# Power.net
KiCad netlist of a schematic drawn in Altium Designer
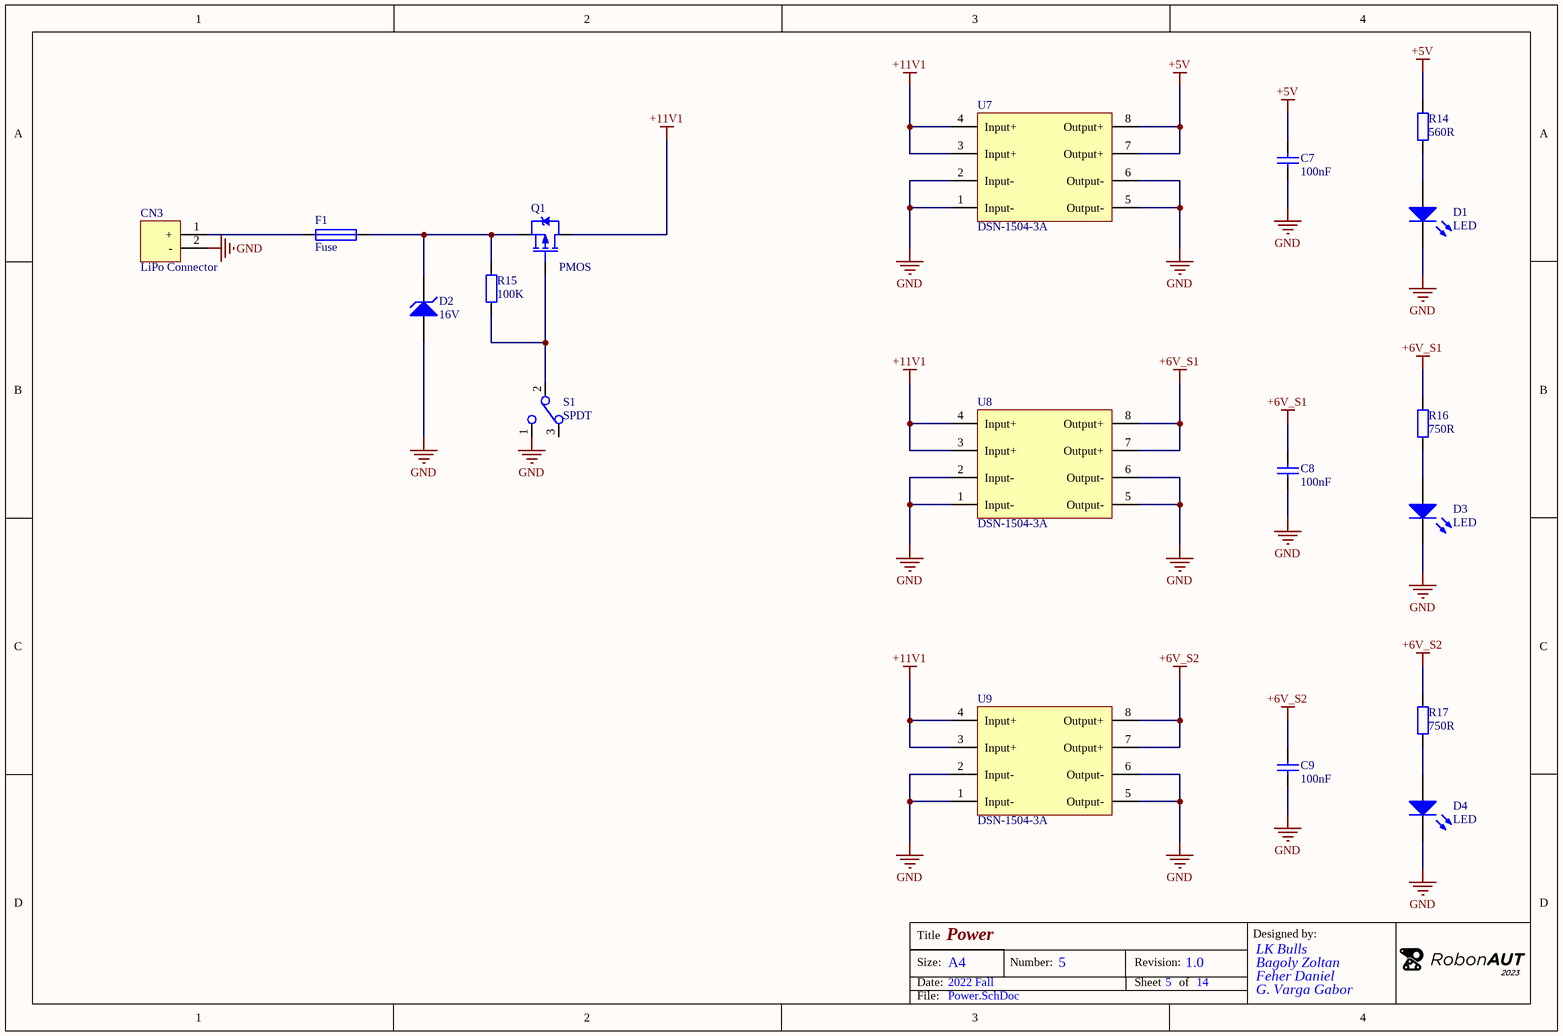
[diagram p0: Power.SchDoc]

(export (version "E")
  (design (tool "Eeschema 10.0.6"))
  (components
    (comp (ref "C7")
      (value "100nF")
      (footprint "FP_0805_CAP_085")
      (description "Capacitor")
      (fields (field (name "TOLERANCE") "10%") (field (name "VOLTAGE") "50V"))
      (libsource (lib "LKBulls2023") (part "CAP"))
    )
    (comp (ref "C8")
      (value "100nF")
      (footprint "FP_0805_CAP_085")
      (description "Capacitor")
      (fields (field (name "TOLERANCE") "10%") (field (name "VOLTAGE") "50V"))
      (libsource (lib "LKBulls2023") (part "CAP"))
    )
    (comp (ref "C9")
      (value "100nF")
      (footprint "FP_0805_CAP_085")
      (description "Capacitor")
      (fields (field (name "TOLERANCE") "10%") (field (name "VOLTAGE") "50V"))
      (libsource (lib "LKBulls2023") (part "CAP"))
    )
    (comp (ref "CN3")
      (value "LiPo Connector")
      (footprint "FP_BATTERY")
      (description "LiPo Battery Connector")
      (libsource (lib "LKBulls2023") (part "Connector_LiPo"))
    )
    (comp (ref "D1")
      (value "LED")
      (footprint "FP_0805_LED_GREEN")
      (description "Typical RED GaAs LED")
      (libsource (lib "LKBulls2023") (part "LED"))
    )
    (comp (ref "D2")
      (value "16V")
      (footprint "FP_SOD-123")
      (description "Zener Diode")
      (libsource (lib "LKBulls2023") (part "ZENER"))
    )
    (comp (ref "D3")
      (value "LED")
      (footprint "FP_0805_LED_GREEN")
      (description "Typical RED GaAs LED")
      (libsource (lib "LKBulls2023") (part "LED"))
    )
    (comp (ref "D4")
      (value "LED")
      (footprint "FP_0805_LED_GREEN")
      (description "Typical RED GaAs LED")
      (libsource (lib "LKBulls2023") (part "LED"))
    )
    (comp (ref "F1")
      (value "Fuse")
      (footprint "FP_CONN2_TUSKE_254MM")
      (libsource (lib "LKBulls2023") (part "Fuse"))
    )
    (comp (ref "Q1")
      (value "PMOS")
      (footprint "FP_DPAK-TO252")
      (description "MOSFET, P CH")
      (libsource (lib "LKBulls2023") (part "PMOS"))
    )
    (comp (ref "R14")
      (value "560R")
      (footprint "FP_0805_RES")
      (description "Resistor")
      (fields (field (name "TOLERANCE") "5%") (field (name "POWER") "0.125W"))
      (libsource (lib "LKBulls2023") (part "RES"))
    )
    (comp (ref "R15")
      (value "100K")
      (footprint "FP_0805_RES")
      (description "Resistor")
      (fields (field (name "TOLERANCE") "5%") (field (name "POWER") "0.125W"))
      (libsource (lib "LKBulls2023") (part "RES"))
    )
    (comp (ref "R16")
      (value "750R")
      (footprint "FP_0805_RES")
      (description "Resistor")
      (fields (field (name "TOLERANCE") "5%") (field (name "POWER") "0.125W"))
      (libsource (lib "LKBulls2023") (part "RES"))
    )
    (comp (ref "R17")
      (value "750R")
      (footprint "FP_0805_RES")
      (description "Resistor")
      (fields (field (name "TOLERANCE") "5%") (field (name "POWER") "0.125W"))
      (libsource (lib "LKBulls2023") (part "RES"))
    )
    (comp (ref "S1")
      (value "SPDT")
      (footprint "FP_SPDT")
      (description "Single-Pole, Double-Throw Switch")
      (libsource (lib "LKBulls2023") (part "SPDT Switch"))
    )
    (comp (ref "U7")
      (value "DSN-1504-3A")
      (footprint "FP_DCDC_DSN")
      (libsource (lib "LKBulls2023") (part "DSN-1504-3A"))
    )
    (comp (ref "U8")
      (value "DSN-1504-3A")
      (footprint "FP_DCDC_DSN")
      (libsource (lib "LKBulls2023") (part "DSN-1504-3A"))
    )
    (comp (ref "U9")
      (value "DSN-1504-3A")
      (footprint "FP_DCDC_DSN")
      (libsource (lib "LKBulls2023") (part "DSN-1504-3A"))
    )
  )
  (nets
    (net (code "1") (name "+5V") (class "Default")
      (node (ref "C7") (pin "2") (pinfunction "2_2") (pintype "passive"))
      (node (ref "R14") (pin "2") (pinfunction "2_2") (pintype "passive"))
      (node (ref "U7") (pin "7") (pinfunction "Output+_7") (pintype "passive"))
      (node (ref "U7") (pin "8") (pinfunction "Output+_8") (pintype "passive"))
    )
    (net (code "2") (name "+6V_S1") (class "Default")
      (node (ref "C8") (pin "2") (pinfunction "2_2") (pintype "passive"))
      (node (ref "R16") (pin "2") (pinfunction "2_2") (pintype "passive"))
      (node (ref "U8") (pin "7") (pinfunction "Output+_7") (pintype "passive"))
      (node (ref "U8") (pin "8") (pinfunction "Output+_8") (pintype "passive"))
    )
    (net (code "3") (name "+6V_S2") (class "Default")
      (node (ref "C9") (pin "2") (pinfunction "2_2") (pintype "passive"))
      (node (ref "R17") (pin "2") (pinfunction "2_2") (pintype "passive"))
      (node (ref "U9") (pin "7") (pinfunction "Output+_7") (pintype "passive"))
      (node (ref "U9") (pin "8") (pinfunction "Output+_8") (pintype "passive"))
    )
    (net (code "4") (name "+11V1") (class "Default")
      (node (ref "Q1") (pin "2") (pinfunction "D_2") (pintype "passive"))
      (node (ref "U7") (pin "3") (pinfunction "Input+_3") (pintype "passive"))
      (node (ref "U7") (pin "4") (pinfunction "Input+_4") (pintype "passive"))
      (node (ref "U8") (pin "3") (pinfunction "Input+_3") (pintype "passive"))
      (node (ref "U8") (pin "4") (pinfunction "Input+_4") (pintype "passive"))
      (node (ref "U9") (pin "3") (pinfunction "Input+_3") (pintype "passive"))
      (node (ref "U9") (pin "4") (pinfunction "Input+_4") (pintype "passive"))
    )
    (net (code "5") (name "GND") (class "Default")
      (node (ref "C7") (pin "1") (pinfunction "1_1") (pintype "passive"))
      (node (ref "C8") (pin "1") (pinfunction "1_1") (pintype "passive"))
      (node (ref "C9") (pin "1") (pinfunction "1_1") (pintype "passive"))
      (node (ref "CN3") (pin "2") (pinfunction "-_2") (pintype "passive"))
      (node (ref "D1") (pin "2") (pinfunction "K_2") (pintype "passive"))
      (node (ref "D2") (pin "A") (pinfunction "1_A") (pintype "passive"))
      (node (ref "D3") (pin "2") (pinfunction "K_2") (pintype "passive"))
      (node (ref "D4") (pin "2") (pinfunction "K_2") (pintype "passive"))
      (node (ref "S1") (pin "1") (pinfunction "C1_1") (pintype "passive"))
      (node (ref "U7") (pin "1") (pinfunction "Input-_1") (pintype "passive"))
      (node (ref "U7") (pin "2") (pinfunction "Input-_2") (pintype "passive"))
      (node (ref "U7") (pin "5") (pinfunction "Output-_5") (pintype "passive"))
      (node (ref "U7") (pin "6") (pinfunction "Output-_6") (pintype "passive"))
      (node (ref "U8") (pin "1") (pinfunction "Input-_1") (pintype "passive"))
      (node (ref "U8") (pin "2") (pinfunction "Input-_2") (pintype "passive"))
      (node (ref "U8") (pin "5") (pinfunction "Output-_5") (pintype "passive"))
      (node (ref "U8") (pin "6") (pinfunction "Output-_6") (pintype "passive"))
      (node (ref "U9") (pin "1") (pinfunction "Input-_1") (pintype "passive"))
      (node (ref "U9") (pin "2") (pinfunction "Input-_2") (pintype "passive"))
      (node (ref "U9") (pin "5") (pinfunction "Output-_5") (pintype "passive"))
      (node (ref "U9") (pin "6") (pinfunction "Output-_6") (pintype "passive"))
    )
    (net (code "6") (name "Net-(CN3-+)") (class "Default")
      (node (ref "CN3") (pin "1") (pinfunction "+_1") (pintype "passive"))
      (node (ref "F1") (pin "1") (pinfunction "1_1") (pintype "passive"))
    )
    (net (code "7") (name "Net-(D1-A)") (class "Default")
      (node (ref "D1") (pin "1") (pinfunction "A_1") (pintype "passive"))
      (node (ref "R14") (pin "1") (pinfunction "1_1") (pintype "passive"))
    )
    (net (code "8") (name "Net-(D2-2)") (class "Default")
      (node (ref "D2") (pin "K") (pinfunction "2_K") (pintype "passive"))
      (node (ref "F1") (pin "2") (pinfunction "2_2") (pintype "passive"))
      (node (ref "Q1") (pin "3") (pinfunction "S_3") (pintype "passive"))
      (node (ref "R15") (pin "2") (pinfunction "2_2") (pintype "passive"))
    )
    (net (code "9") (name "Net-(D3-A)") (class "Default")
      (node (ref "D3") (pin "1") (pinfunction "A_1") (pintype "passive"))
      (node (ref "R16") (pin "1") (pinfunction "1_1") (pintype "passive"))
    )
    (net (code "10") (name "Net-(D4-A)") (class "Default")
      (node (ref "D4") (pin "1") (pinfunction "A_1") (pintype "passive"))
      (node (ref "R17") (pin "1") (pinfunction "1_1") (pintype "passive"))
    )
    (net (code "11") (name "Net-(Q1-G)") (class "Default")
      (node (ref "Q1") (pin "1") (pinfunction "G_1") (pintype "passive"))
      (node (ref "R15") (pin "1") (pinfunction "1_1") (pintype "passive"))
      (node (ref "S1") (pin "2") (pinfunction "C2_2") (pintype "passive"))
    )
    (net (code "12") (name "unconnected-(S1-C3-Pad3)") (class "Default")
      (node (ref "S1") (pin "3") (pinfunction "C3_3") (pintype "passive"))
    )
  )
)
